# 140716_AriloTX_REV3_0_0_433MHZ_td.net
KiCad netlist of a schematic drawn in EAGLE
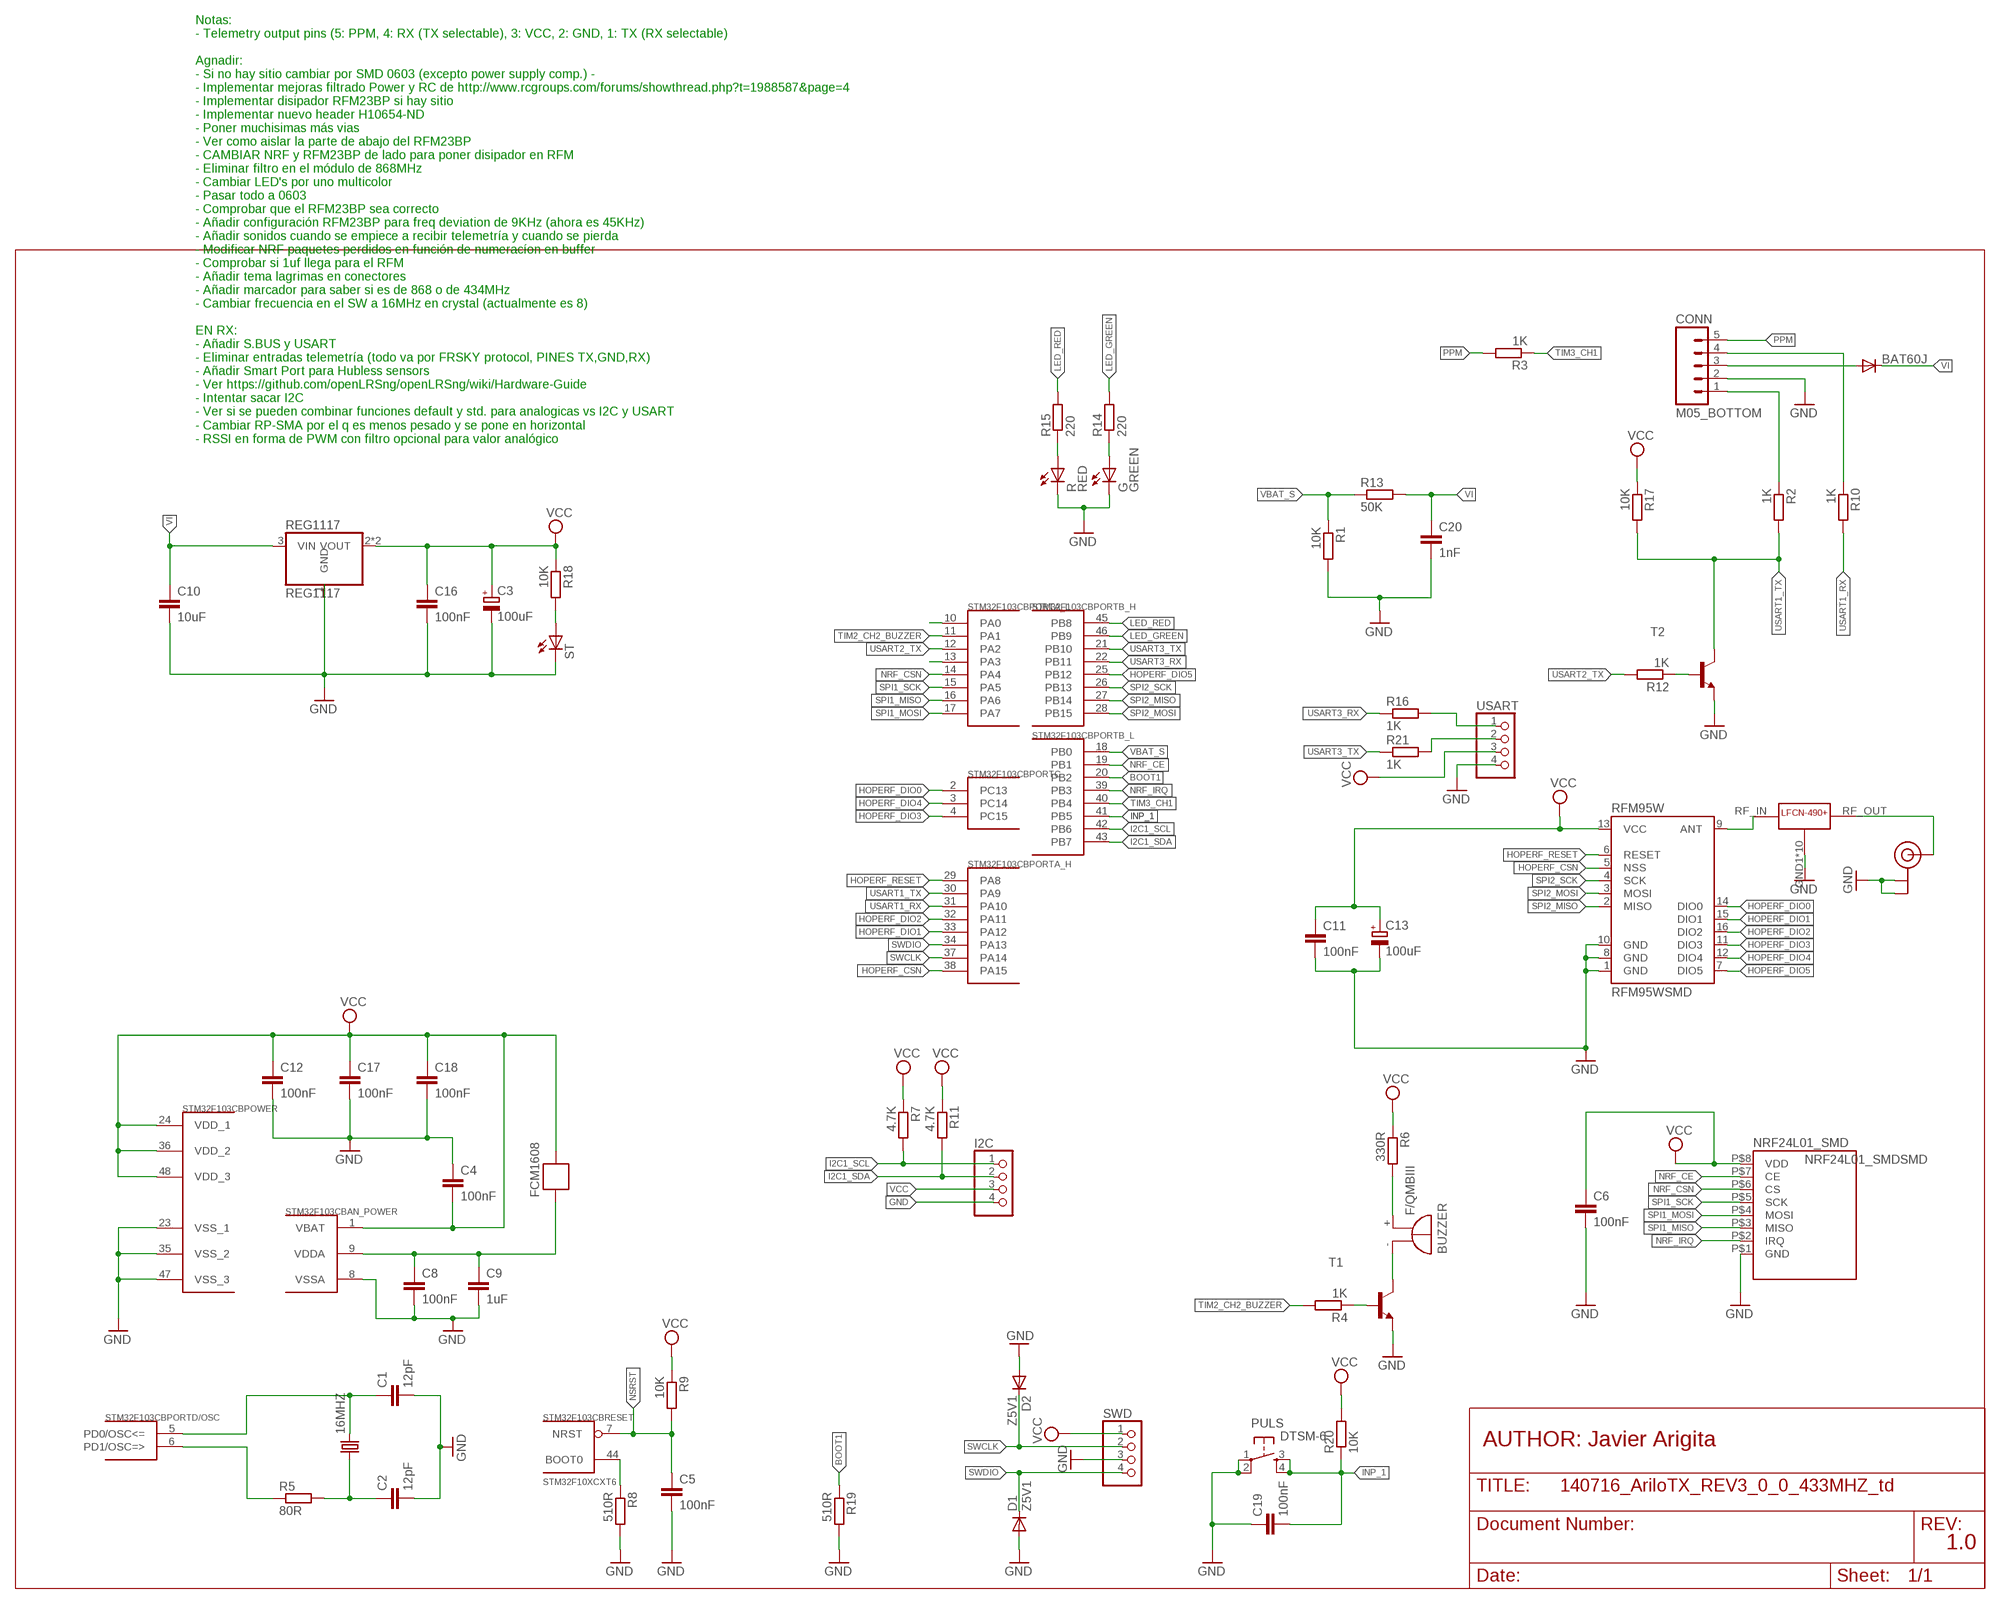
[diagram p0: schematic, sheet 1]

(export (version "E")
  (design (tool "Eeschema 10.0.6"))
  (components
    (comp (ref "16MHZ")
      (value "CRYSTAL5X3")
      (footprint "eagle-import:CRYSTAL-SMD-5X3")
      (libsource (lib "eagle-import") (part "CRYSTAL5X3"))
    )
    (comp (ref "BAT60J")
      (value "DIODE-SOD323-R")
      (footprint "eagle-import:SOD323-R")
      (libsource (lib "eagle-import") (part "DIODE-SOD323-R"))
    )
    (comp (ref "BUZZER")
      (value "F/QMBIII")
      (footprint "eagle-import:F_QMBIII")
      (libsource (lib "eagle-import") (part "F/QMBIII"))
    )
    (comp (ref "C1")
      (value "12pF")
      (footprint "eagle-import:C0603")
      (libsource (lib "eagle-import") (part "C-EUC0603"))
    )
    (comp (ref "C2")
      (value "12pF")
      (footprint "eagle-import:C0603")
      (libsource (lib "eagle-import") (part "C-EUC0603"))
    )
    (comp (ref "C3")
      (value "100uF")
      (footprint "eagle-import:SMC_B")
      (libsource (lib "eagle-import") (part "CPOL-EUSMCB"))
    )
    (comp (ref "C4")
      (value "100nF")
      (footprint "eagle-import:C0603")
      (libsource (lib "eagle-import") (part "C-EUC0603"))
    )
    (comp (ref "C5")
      (value "100nF")
      (footprint "eagle-import:C0603")
      (libsource (lib "eagle-import") (part "C-EUC0603"))
    )
    (comp (ref "C6")
      (value "100nF")
      (footprint "eagle-import:C0603")
      (libsource (lib "eagle-import") (part "C-EUC0603"))
    )
    (comp (ref "C8")
      (value "100nF")
      (footprint "eagle-import:C0603")
      (libsource (lib "eagle-import") (part "C-EUC0603"))
    )
    (comp (ref "C9")
      (value "1uF")
      (footprint "eagle-import:C0603")
      (libsource (lib "eagle-import") (part "C-EUC0603"))
    )
    (comp (ref "C10")
      (value "10uF")
      (footprint "eagle-import:C3216")
      (libsource (lib "eagle-import") (part "resistor_C-EUC3216"))
    )
    (comp (ref "C11")
      (value "100nF")
      (footprint "eagle-import:C0603")
      (libsource (lib "eagle-import") (part "C-EUC0603"))
    )
    (comp (ref "C12")
      (value "100nF")
      (footprint "eagle-import:C0603")
      (libsource (lib "eagle-import") (part "C-EUC0603"))
    )
    (comp (ref "C13")
      (value "100uF")
      (footprint "eagle-import:SMC_B")
      (libsource (lib "eagle-import") (part "CPOL-EUSMCB"))
    )
    (comp (ref "C16")
      (value "100nF")
      (footprint "eagle-import:C0603")
      (libsource (lib "eagle-import") (part "C-EUC0603"))
    )
    (comp (ref "C17")
      (value "100nF")
      (footprint "eagle-import:C0603")
      (libsource (lib "eagle-import") (part "C-EUC0603"))
    )
    (comp (ref "C18")
      (value "100nF")
      (footprint "eagle-import:C0603")
      (libsource (lib "eagle-import") (part "C-EUC0603"))
    )
    (comp (ref "C19")
      (value "100nF")
      (footprint "eagle-import:C0603")
      (libsource (lib "eagle-import") (part "C-EUC0603"))
    )
    (comp (ref "C20")
      (value "1nF")
      (footprint "eagle-import:C0603")
      (libsource (lib "eagle-import") (part "C-EUC0603"))
    )
    (comp (ref "CONN")
      (value "M05_BOTTOM")
      (footprint "eagle-import:M05_BOTTOM")
      (libsource (lib "eagle-import") (part "M05_BOTTOM"))
    )
    (comp (ref "D1")
      (value "Z5V1")
      (footprint "eagle-import:SOD323-R")
      (libsource (lib "eagle-import") (part "DIODE-SOD323-R"))
    )
    (comp (ref "D2")
      (value "Z5V1")
      (footprint "eagle-import:SOD323-R")
      (libsource (lib "eagle-import") (part "DIODE-SOD323-R"))
    )
    (comp (ref "FCM1608")
      (value "FERRITE-BEAD")
      (footprint "eagle-import:R0603")
      (libsource (lib "eagle-import") (part "FERRITE-BEAD"))
    )
    (comp (ref "G")
      (value "GREEN")
      (footprint "eagle-import:CHIP-LED0603")
      (libsource (lib "eagle-import") (part "LEDCHIP-LED0603"))
    )
    (comp (ref "I2C")
      (value "PINHD-1X4")
      (footprint "eagle-import:1X04")
      (libsource (lib "eagle-import") (part "PINHD-1X4"))
    )
    (comp (ref "LFCN490+")
      (value "LFCN490+")
      (footprint "eagle-import:LFCN490+")
      (libsource (lib "eagle-import") (part "LFCN490+"))
    )
    (comp (ref "NRF24L01_SMD")
      (value "NRF24L01_SMDSMD")
      (footprint "eagle-import:NRF24L01_SMD")
      (libsource (lib "eagle-import") (part "NRF24L01_SMDSMD"))
    )
    (comp (ref "PULS")
      (value "DTSM-6")
      (footprint "eagle-import:DTSM-6")
      (libsource (lib "eagle-import") (part "DTSM-6"))
    )
    (comp (ref "R")
      (value "RED")
      (footprint "eagle-import:CHIP-LED0603")
      (libsource (lib "eagle-import") (part "LEDCHIP-LED0603"))
    )
    (comp (ref "R1")
      (value "10K")
      (footprint "eagle-import:R0603")
      (libsource (lib "eagle-import") (part "R-EU_R0603"))
    )
    (comp (ref "R2")
      (value "1K")
      (footprint "eagle-import:R0603")
      (libsource (lib "eagle-import") (part "R-EU_R0603"))
    )
    (comp (ref "R3")
      (value "1K")
      (footprint "eagle-import:R0603")
      (libsource (lib "eagle-import") (part "R-EU_R0603"))
    )
    (comp (ref "R4")
      (value "1K")
      (footprint "eagle-import:R0603")
      (libsource (lib "eagle-import") (part "R-EU_R0603"))
    )
    (comp (ref "R5")
      (value "80R")
      (footprint "eagle-import:R0603")
      (libsource (lib "eagle-import") (part "R-EU_R0603"))
    )
    (comp (ref "R6")
      (value "330R")
      (footprint "eagle-import:R0603")
      (libsource (lib "eagle-import") (part "R-EU_R0603"))
    )
    (comp (ref "R7")
      (value "4.7K")
      (footprint "eagle-import:R0603")
      (libsource (lib "eagle-import") (part "R-EU_R0603"))
    )
    (comp (ref "R8")
      (value "510R")
      (footprint "eagle-import:R0603")
      (libsource (lib "eagle-import") (part "R-EU_R0603"))
    )
    (comp (ref "R9")
      (value "10K")
      (footprint "eagle-import:R0603")
      (libsource (lib "eagle-import") (part "R-EU_R0603"))
    )
    (comp (ref "R10")
      (value "1K")
      (footprint "eagle-import:R0603")
      (libsource (lib "eagle-import") (part "R-EU_R0603"))
    )
    (comp (ref "R11")
      (value "4.7K")
      (footprint "eagle-import:R0603")
      (libsource (lib "eagle-import") (part "R-EU_R0603"))
    )
    (comp (ref "R12")
      (value "1K")
      (footprint "eagle-import:R0603")
      (libsource (lib "eagle-import") (part "R-EU_R0603"))
    )
    (comp (ref "R13")
      (value "50K")
      (footprint "eagle-import:R0603")
      (libsource (lib "eagle-import") (part "R-EU_R0603"))
    )
    (comp (ref "R14")
      (value "220")
      (footprint "eagle-import:R0603")
      (libsource (lib "eagle-import") (part "R-EU_R0603"))
    )
    (comp (ref "R15")
      (value "220")
      (footprint "eagle-import:R0603")
      (libsource (lib "eagle-import") (part "R-EU_R0603"))
    )
    (comp (ref "R16")
      (value "1K")
      (footprint "eagle-import:R0603")
      (libsource (lib "eagle-import") (part "R-EU_R0603"))
    )
    (comp (ref "R17")
      (value "10K")
      (footprint "eagle-import:R0603")
      (libsource (lib "eagle-import") (part "R-EU_R0603"))
    )
    (comp (ref "R18")
      (value "10K")
      (footprint "eagle-import:R0603")
      (libsource (lib "eagle-import") (part "R-EU_R0603"))
    )
    (comp (ref "R19")
      (value "510R")
      (footprint "eagle-import:R0603")
      (libsource (lib "eagle-import") (part "R-EU_R0603"))
    )
    (comp (ref "R20")
      (value "10K")
      (footprint "eagle-import:R0603")
      (libsource (lib "eagle-import") (part "R-EU_R0603"))
    )
    (comp (ref "R21")
      (value "1K")
      (footprint "eagle-import:R0603")
      (libsource (lib "eagle-import") (part "R-EU_R0603"))
    )
    (comp (ref "REG1117")
      (value "REG1117")
      (footprint "eagle-import:SOT223")
      (libsource (lib "eagle-import") (part "REG1117"))
    )
    (comp (ref "RFM95W")
      (value "RFM95WSMD")
      (footprint "eagle-import:MISIEK_RFM95W_SMD")
      (libsource (lib "eagle-import") (part "MISIEK_RFM95WSMD"))
    )
    (comp (ref "ST")
      (value "LEDCHIP-LED0603")
      (footprint "eagle-import:CHIP-LED0603")
      (libsource (lib "eagle-import") (part "LEDCHIP-LED0603"))
    )
    (comp (ref "STM32F103CB")
      (value "STM32F10XCXT6")
      (footprint "eagle-import:TQFP48")
      (libsource (lib "eagle-import") (part "STM32F10XCXT6"))
    )
    (comp (ref "SWD")
      (value "PINHD-1X4")
      (footprint "eagle-import:1X04")
      (libsource (lib "eagle-import") (part "PINHD-1X4"))
    )
    (comp (ref "T1")
      (value "BC848-NPN-SOT23-BEC")
      (footprint "eagle-import:SOT23-BEC")
      (libsource (lib "eagle-import") (part "-NPN-SOT23-BECBC848"))
    )
    (comp (ref "T2")
      (value "BC848-NPN-SOT23-BEC")
      (footprint "eagle-import:SOT23-BEC")
      (libsource (lib "eagle-import") (part "-NPN-SOT23-BECBC848"))
    )
    (comp (ref "U.FL")
      (value "U.FL")
      (footprint "eagle-import:U.FL")
      (libsource (lib "eagle-import") (part "U.FL"))
    )
    (comp (ref "USART")
      (value "PINHD-1X4")
      (footprint "eagle-import:1X04")
      (libsource (lib "eagle-import") (part "PINHD-1X4"))
    )
  )
  (nets
    (net (code "1") (name "BOOT1") (class "Default")
      (node (ref "R19") (pin "1") (pinfunction "1_1") (pintype "passive"))
      (node (ref "STM32F103CB") (pin "20") (pinfunction "PB2_20") (pintype "bidirectional"))
    )
    (net (code "2") (name "GND") (class "Default")
      (node (ref "C1") (pin "2") (pinfunction "2_2") (pintype "passive"))
      (node (ref "C10") (pin "2") (pinfunction "2_2") (pintype "passive"))
      (node (ref "C11") (pin "2") (pinfunction "2_2") (pintype "passive"))
      (node (ref "C12") (pin "2") (pinfunction "2_2") (pintype "passive"))
      (node (ref "C13") (pin "-") (pinfunction "-_-") (pintype "passive"))
      (node (ref "C16") (pin "2") (pinfunction "2_2") (pintype "passive"))
      (node (ref "C17") (pin "2") (pinfunction "2_2") (pintype "passive"))
      (node (ref "C18") (pin "2") (pinfunction "2_2") (pintype "passive"))
      (node (ref "C19") (pin "1") (pinfunction "1_1") (pintype "passive"))
      (node (ref "C2") (pin "2") (pinfunction "2_2") (pintype "passive"))
      (node (ref "C20") (pin "2") (pinfunction "2_2") (pintype "passive"))
      (node (ref "C3") (pin "-") (pinfunction "-_-") (pintype "passive"))
      (node (ref "C4") (pin "1") (pinfunction "1_1") (pintype "passive"))
      (node (ref "C5") (pin "2") (pinfunction "2_2") (pintype "passive"))
      (node (ref "C6") (pin "2") (pinfunction "2_2") (pintype "passive"))
      (node (ref "C8") (pin "2") (pinfunction "2_2") (pintype "passive"))
      (node (ref "C9") (pin "2") (pinfunction "2_2") (pintype "passive"))
      (node (ref "CONN") (pin "2") (pinfunction "2_2") (pintype "passive"))
      (node (ref "D1") (pin "A") (pinfunction "A_A") (pintype "passive"))
      (node (ref "D2") (pin "A") (pinfunction "A_A") (pintype "passive"))
      (node (ref "G") (pin "C") (pinfunction "C_C") (pintype "passive"))
      (node (ref "I2C") (pin "4") (pinfunction "4_4") (pintype "passive"))
      (node (ref "LFCN490+") (pin "GND1") (pinfunction "GND_GND1") (pintype "bidirectional"))
      (node (ref "LFCN490+") (pin "GND10") (pinfunction "GND_GND10") (pintype "bidirectional"))
      (node (ref "LFCN490+") (pin "GND2") (pinfunction "GND_GND2") (pintype "bidirectional"))
      (node (ref "LFCN490+") (pin "GND3") (pinfunction "GND_GND3") (pintype "bidirectional"))
      (node (ref "LFCN490+") (pin "GND4") (pinfunction "GND_GND4") (pintype "bidirectional"))
      (node (ref "LFCN490+") (pin "GND5") (pinfunction "GND_GND5") (pintype "bidirectional"))
      (node (ref "LFCN490+") (pin "GND6") (pinfunction "GND_GND6") (pintype "bidirectional"))
      (node (ref "LFCN490+") (pin "GND7") (pinfunction "GND_GND7") (pintype "bidirectional"))
      (node (ref "LFCN490+") (pin "GND8") (pinfunction "GND_GND8") (pintype "bidirectional"))
      (node (ref "LFCN490+") (pin "GND9") (pinfunction "GND_GND9") (pintype "bidirectional"))
      (node (ref "NRF24L01_SMD") (pin "P$1") (pinfunction "GND_P$1") (pintype "power_in"))
      (node (ref "PULS") (pin "1") (pinfunction "1_1") (pintype "passive"))
      (node (ref "PULS") (pin "2") (pinfunction "2_2") (pintype "passive"))
      (node (ref "R") (pin "C") (pinfunction "C_C") (pintype "passive"))
      (node (ref "R1") (pin "2") (pinfunction "2_2") (pintype "passive"))
      (node (ref "R19") (pin "2") (pinfunction "2_2") (pintype "passive"))
      (node (ref "R8") (pin "2") (pinfunction "2_2") (pintype "passive"))
      (node (ref "REG1117") (pin "1") (pinfunction "GND_1") (pintype "power_in"))
      (node (ref "RFM95W") (pin "1") (pinfunction "GND_1") (pintype "power_in"))
      (node (ref "RFM95W") (pin "10") (pinfunction "GND_10") (pintype "power_in"))
      (node (ref "RFM95W") (pin "8") (pinfunction "GND_8") (pintype "power_in"))
      (node (ref "ST") (pin "C") (pinfunction "C_C") (pintype "passive"))
      (node (ref "STM32F103CB") (pin "23") (pinfunction "VSS_1_23") (pintype "power_in"))
      (node (ref "STM32F103CB") (pin "35") (pinfunction "VSS_2_35") (pintype "power_in"))
      (node (ref "STM32F103CB") (pin "47") (pinfunction "VSS_3_47") (pintype "power_in"))
      (node (ref "STM32F103CB") (pin "8") (pinfunction "VSSA_8") (pintype "power_in"))
      (node (ref "SWD") (pin "3") (pinfunction "3_3") (pintype "passive"))
      (node (ref "T1") (pin "E") (pinfunction "E_E") (pintype "passive"))
      (node (ref "T2") (pin "E") (pinfunction "E_E") (pintype "passive"))
      (node (ref "U.FL") (pin "P$1") (pinfunction "GND_P$1") (pintype "bidirectional"))
      (node (ref "U.FL") (pin "P$2") (pinfunction "GND_P$2") (pintype "bidirectional"))
      (node (ref "USART") (pin "4") (pinfunction "4_4") (pintype "passive"))
    )
    (net (code "3") (name "HOPERF_CSN") (class "Default")
      (node (ref "RFM95W") (pin "5") (pinfunction "NSS_5") (pintype "input"))
      (node (ref "STM32F103CB") (pin "38") (pinfunction "PA15_38") (pintype "bidirectional"))
    )
    (net (code "4") (name "HOPERF_DIO0") (class "Default")
      (node (ref "RFM95W") (pin "14") (pinfunction "DIO0_14") (pintype "input"))
      (node (ref "STM32F103CB") (pin "2") (pinfunction "PC13_2") (pintype "bidirectional"))
    )
    (net (code "5") (name "HOPERF_DIO1") (class "Default")
      (node (ref "RFM95W") (pin "15") (pinfunction "DIO1_15") (pintype "input"))
      (node (ref "STM32F103CB") (pin "33") (pinfunction "PA12_33") (pintype "bidirectional"))
    )
    (net (code "6") (name "HOPERF_DIO2") (class "Default")
      (node (ref "RFM95W") (pin "16") (pinfunction "DIO2_16") (pintype "input"))
      (node (ref "STM32F103CB") (pin "32") (pinfunction "PA11_32") (pintype "bidirectional"))
    )
    (net (code "7") (name "HOPERF_DIO3") (class "Default")
      (node (ref "RFM95W") (pin "11") (pinfunction "DIO3_11") (pintype "bidirectional"))
      (node (ref "STM32F103CB") (pin "4") (pinfunction "PC15_4") (pintype "bidirectional"))
    )
    (net (code "8") (name "HOPERF_DIO4") (class "Default")
      (node (ref "RFM95W") (pin "12") (pinfunction "DIO4_12") (pintype "bidirectional"))
      (node (ref "STM32F103CB") (pin "3") (pinfunction "PC14_3") (pintype "bidirectional"))
    )
    (net (code "9") (name "HOPERF_DIO5") (class "Default")
      (node (ref "RFM95W") (pin "7") (pinfunction "DIO5_7") (pintype "bidirectional"))
      (node (ref "STM32F103CB") (pin "25") (pinfunction "PB12_25") (pintype "bidirectional"))
    )
    (net (code "10") (name "HOPERF_RESET") (class "Default")
      (node (ref "RFM95W") (pin "6") (pinfunction "RESET_6") (pintype "output"))
      (node (ref "STM32F103CB") (pin "29") (pinfunction "PA8_29") (pintype "bidirectional"))
    )
    (net (code "11") (name "I2C1_SCL") (class "Default")
      (node (ref "I2C") (pin "1") (pinfunction "1_1") (pintype "passive"))
      (node (ref "R7") (pin "2") (pinfunction "2_2") (pintype "passive"))
      (node (ref "STM32F103CB") (pin "42") (pinfunction "PB6_42") (pintype "bidirectional"))
    )
    (net (code "12") (name "I2C1_SDA") (class "Default")
      (node (ref "I2C") (pin "2") (pinfunction "2_2") (pintype "passive"))
      (node (ref "R11") (pin "2") (pinfunction "2_2") (pintype "passive"))
      (node (ref "STM32F103CB") (pin "43") (pinfunction "PB7_43") (pintype "bidirectional"))
    )
    (net (code "13") (name "INP_1") (class "Default")
      (node (ref "C19") (pin "2") (pinfunction "2_2") (pintype "passive"))
      (node (ref "PULS") (pin "3") (pinfunction "3_3") (pintype "passive"))
      (node (ref "PULS") (pin "4") (pinfunction "4_4") (pintype "passive"))
      (node (ref "R20") (pin "1") (pinfunction "1_1") (pintype "passive"))
      (node (ref "STM32F103CB") (pin "41") (pinfunction "PB5_41") (pintype "bidirectional"))
    )
    (net (code "14") (name "LED_GREEN") (class "Default")
      (node (ref "R14") (pin "2") (pinfunction "2_2") (pintype "passive"))
      (node (ref "STM32F103CB") (pin "46") (pinfunction "PB9_46") (pintype "bidirectional"))
    )
    (net (code "15") (name "LED_RED") (class "Default")
      (node (ref "R15") (pin "2") (pinfunction "2_2") (pintype "passive"))
      (node (ref "STM32F103CB") (pin "45") (pinfunction "PB8_45") (pintype "bidirectional"))
    )
    (net (code "16") (name "NRF_CE") (class "Default")
      (node (ref "NRF24L01_SMD") (pin "P$7") (pinfunction "CE_P$7") (pintype "input"))
      (node (ref "STM32F103CB") (pin "19") (pinfunction "PB1_19") (pintype "bidirectional"))
    )
    (net (code "17") (name "NRF_CSN") (class "Default")
      (node (ref "NRF24L01_SMD") (pin "P$6") (pinfunction "CS_P$6") (pintype "input"))
      (node (ref "STM32F103CB") (pin "14") (pinfunction "PA4_14") (pintype "bidirectional"))
    )
    (net (code "18") (name "NRF_IRQ") (class "Default")
      (node (ref "NRF24L01_SMD") (pin "P$2") (pinfunction "IRQ_P$2") (pintype "output"))
      (node (ref "STM32F103CB") (pin "39") (pinfunction "PB3_39") (pintype "bidirectional"))
    )
    (net (code "19") (name "NSRST") (class "Default")
      (node (ref "C5") (pin "1") (pinfunction "1_1") (pintype "passive"))
      (node (ref "R9") (pin "2") (pinfunction "2_2") (pintype "passive"))
      (node (ref "STM32F103CB") (pin "7") (pinfunction "NRST_7") (pintype "input"))
    )
    (net (code "20") (name "Net-(16MHZ-2)") (class "Default")
      (node (ref "16MHZ") (pin "3") (pinfunction "2_3") (pintype "passive"))
      (node (ref "C1") (pin "1") (pinfunction "1_1") (pintype "passive"))
      (node (ref "STM32F103CB") (pin "5") (pinfunction "PD0/OSC<=_5") (pintype "bidirectional"))
    )
    (net (code "21") (name "Net-(16MHZ-Pad1)") (class "Default")
      (node (ref "16MHZ") (pin "1") (pinfunction "1_1") (pintype "passive"))
      (node (ref "C2") (pin "1") (pinfunction "1_1") (pintype "passive"))
      (node (ref "R5") (pin "2") (pinfunction "2_2") (pintype "passive"))
    )
    (net (code "22") (name "Net-(BAT60J-PadA)") (class "Default")
      (node (ref "BAT60J") (pin "A") (pinfunction "A_A") (pintype "passive"))
      (node (ref "CONN") (pin "3") (pinfunction "3_3") (pintype "passive"))
    )
    (net (code "23") (name "Net-(BUZZER-+)") (class "Default")
      (node (ref "BUZZER") (pin "-") (pinfunction "+_-") (pintype "passive"))
      (node (ref "T1") (pin "C") (pinfunction "C_C") (pintype "passive"))
    )
    (net (code "24") (name "Net-(BUZZER--)") (class "Default")
      (node (ref "BUZZER") (pin "+") (pinfunction "-_+") (pintype "passive"))
      (node (ref "R6") (pin "2") (pinfunction "2_2") (pintype "passive"))
    )
    (net (code "25") (name "Net-(CONN-Pad1)") (class "Default")
      (node (ref "CONN") (pin "1") (pinfunction "1_1") (pintype "passive"))
      (node (ref "R2") (pin "1") (pinfunction "1_1") (pintype "passive"))
    )
    (net (code "26") (name "Net-(CONN-Pad4)") (class "Default")
      (node (ref "CONN") (pin "4") (pinfunction "4_4") (pintype "passive"))
      (node (ref "R10") (pin "1") (pinfunction "1_1") (pintype "passive"))
    )
    (net (code "27") (name "Net-(FCM1608-P$2)") (class "Default")
      (node (ref "C8") (pin "1") (pinfunction "1_1") (pintype "passive"))
      (node (ref "C9") (pin "1") (pinfunction "1_1") (pintype "passive"))
      (node (ref "FCM1608") (pin "2") (pinfunction "P$2_2") (pintype "bidirectional"))
      (node (ref "STM32F103CB") (pin "9") (pinfunction "VDDA_9") (pintype "power_in"))
    )
    (net (code "28") (name "Net-(G-PadA)") (class "Default")
      (node (ref "G") (pin "A") (pinfunction "A_A") (pintype "passive"))
      (node (ref "R14") (pin "1") (pinfunction "1_1") (pintype "passive"))
    )
    (net (code "29") (name "Net-(LFCN490+-RF_INP)") (class "Default")
      (node (ref "LFCN490+") (pin "RF_IN") (pinfunction "RF_INP_RF_IN") (pintype "bidirectional"))
      (node (ref "RFM95W") (pin "9") (pinfunction "ANT_9") (pintype "bidirectional"))
    )
    (net (code "30") (name "Net-(LFCN490+-RF_OUTP)") (class "Default")
      (node (ref "LFCN490+") (pin "RF_OUT") (pinfunction "RF_OUTP_RF_OUT") (pintype "bidirectional"))
      (node (ref "U.FL") (pin "P$3") (pinfunction "SIGNAL_P$3") (pintype "bidirectional"))
    )
    (net (code "31") (name "Net-(R-PadA)") (class "Default")
      (node (ref "R") (pin "A") (pinfunction "A_A") (pintype "passive"))
      (node (ref "R15") (pin "1") (pinfunction "1_1") (pintype "passive"))
    )
    (net (code "32") (name "Net-(R4-Pad1)") (class "Default")
      (node (ref "R4") (pin "1") (pinfunction "1_1") (pintype "passive"))
      (node (ref "T1") (pin "B") (pinfunction "B_B") (pintype "passive"))
    )
    (net (code "33") (name "Net-(R12-Pad1)") (class "Default")
      (node (ref "R12") (pin "1") (pinfunction "1_1") (pintype "passive"))
      (node (ref "T2") (pin "B") (pinfunction "B_B") (pintype "passive"))
    )
    (net (code "34") (name "Net-(R16-Pad2)") (class "Default")
      (node (ref "R16") (pin "2") (pinfunction "2_2") (pintype "passive"))
      (node (ref "USART") (pin "1") (pinfunction "1_1") (pintype "passive"))
    )
    (net (code "35") (name "Net-(R18-Pad2)") (class "Default")
      (node (ref "R18") (pin "2") (pinfunction "2_2") (pintype "passive"))
      (node (ref "ST") (pin "A") (pinfunction "A_A") (pintype "passive"))
    )
    (net (code "36") (name "Net-(R21-Pad2)") (class "Default")
      (node (ref "R21") (pin "2") (pinfunction "2_2") (pintype "passive"))
      (node (ref "USART") (pin "2") (pinfunction "2_2") (pintype "passive"))
    )
    (net (code "37") (name "Net-(STM32F103CBG-PD1{slash}OSC=>)") (class "Default")
      (node (ref "R5") (pin "1") (pinfunction "1_1") (pintype "passive"))
      (node (ref "STM32F103CB") (pin "6") (pinfunction "PD1/OSC=>_6") (pintype "bidirectional"))
    )
    (net (code "38") (name "Net-(STM32F103CBI-BOOT0)") (class "Default")
      (node (ref "R8") (pin "1") (pinfunction "1_1") (pintype "passive"))
      (node (ref "STM32F103CB") (pin "44") (pinfunction "BOOT0_44") (pintype "input"))
    )
    (net (code "39") (name "PPM") (class "Default")
      (node (ref "CONN") (pin "5") (pinfunction "5_5") (pintype "passive"))
      (node (ref "R3") (pin "2") (pinfunction "2_2") (pintype "passive"))
    )
    (net (code "40") (name "SPI1_MISO") (class "Default")
      (node (ref "NRF24L01_SMD") (pin "P$3") (pinfunction "MISO_P$3") (pintype "output"))
      (node (ref "STM32F103CB") (pin "16") (pinfunction "PA6_16") (pintype "bidirectional"))
    )
    (net (code "41") (name "SPI1_MOSI") (class "Default")
      (node (ref "NRF24L01_SMD") (pin "P$4") (pinfunction "MOSI_P$4") (pintype "input"))
      (node (ref "STM32F103CB") (pin "17") (pinfunction "PA7_17") (pintype "bidirectional"))
    )
    (net (code "42") (name "SPI1_SCK") (class "Default")
      (node (ref "NRF24L01_SMD") (pin "P$5") (pinfunction "SCK_P$5") (pintype "input"))
      (node (ref "STM32F103CB") (pin "15") (pinfunction "PA5_15") (pintype "bidirectional"))
    )
    (net (code "43") (name "SPI2_MISO") (class "Default")
      (node (ref "RFM95W") (pin "2") (pinfunction "MISO_2") (pintype "output"))
      (node (ref "STM32F103CB") (pin "27") (pinfunction "PB14_27") (pintype "bidirectional"))
    )
    (net (code "44") (name "SPI2_MOSI") (class "Default")
      (node (ref "RFM95W") (pin "3") (pinfunction "MOSI_3") (pintype "input"))
      (node (ref "STM32F103CB") (pin "28") (pinfunction "PB15_28") (pintype "bidirectional"))
    )
    (net (code "45") (name "SPI2_SCK") (class "Default")
      (node (ref "RFM95W") (pin "4") (pinfunction "SCK_4") (pintype "input"))
      (node (ref "STM32F103CB") (pin "26") (pinfunction "PB13_26") (pintype "bidirectional"))
    )
    (net (code "46") (name "SWCLK") (class "Default")
      (node (ref "D2") (pin "C") (pinfunction "C_C") (pintype "passive"))
      (node (ref "STM32F103CB") (pin "37") (pinfunction "PA14_37") (pintype "bidirectional"))
      (node (ref "SWD") (pin "2") (pinfunction "2_2") (pintype "passive"))
    )
    (net (code "47") (name "SWDIO") (class "Default")
      (node (ref "D1") (pin "C") (pinfunction "C_C") (pintype "passive"))
      (node (ref "STM32F103CB") (pin "34") (pinfunction "PA13_34") (pintype "bidirectional"))
      (node (ref "SWD") (pin "4") (pinfunction "4_4") (pintype "passive"))
    )
    (net (code "48") (name "TIM2_CH2_BUZZER") (class "Default")
      (node (ref "R4") (pin "2") (pinfunction "2_2") (pintype "passive"))
      (node (ref "STM32F103CB") (pin "11") (pinfunction "PA1_11") (pintype "bidirectional"))
    )
    (net (code "49") (name "TIM3_CH1") (class "Default")
      (node (ref "R3") (pin "1") (pinfunction "1_1") (pintype "passive"))
      (node (ref "STM32F103CB") (pin "40") (pinfunction "PB4_40") (pintype "bidirectional"))
    )
    (net (code "50") (name "USART1_RX") (class "Default")
      (node (ref "R10") (pin "2") (pinfunction "2_2") (pintype "passive"))
      (node (ref "STM32F103CB") (pin "31") (pinfunction "PA10_31") (pintype "bidirectional"))
    )
    (net (code "51") (name "USART1_TX") (class "Default")
      (node (ref "R17") (pin "2") (pinfunction "2_2") (pintype "passive"))
      (node (ref "R2") (pin "2") (pinfunction "2_2") (pintype "passive"))
      (node (ref "STM32F103CB") (pin "30") (pinfunction "PA9_30") (pintype "bidirectional"))
      (node (ref "T2") (pin "C") (pinfunction "C_C") (pintype "passive"))
    )
    (net (code "52") (name "USART2_TX") (class "Default")
      (node (ref "R12") (pin "2") (pinfunction "2_2") (pintype "passive"))
      (node (ref "STM32F103CB") (pin "12") (pinfunction "PA2_12") (pintype "bidirectional"))
    )
    (net (code "53") (name "USART3_RX") (class "Default")
      (node (ref "R16") (pin "1") (pinfunction "1_1") (pintype "passive"))
      (node (ref "STM32F103CB") (pin "22") (pinfunction "PB11_22") (pintype "bidirectional"))
    )
    (net (code "54") (name "USART3_TX") (class "Default")
      (node (ref "R21") (pin "1") (pinfunction "1_1") (pintype "passive"))
      (node (ref "STM32F103CB") (pin "21") (pinfunction "PB10_21") (pintype "bidirectional"))
    )
    (net (code "55") (name "VBAT_S") (class "Default")
      (node (ref "R1") (pin "1") (pinfunction "1_1") (pintype "passive"))
      (node (ref "R13") (pin "1") (pinfunction "1_1") (pintype "passive"))
      (node (ref "STM32F103CB") (pin "18") (pinfunction "PB0_18") (pintype "bidirectional"))
    )
    (net (code "56") (name "VCC") (class "Default")
      (node (ref "C11") (pin "1") (pinfunction "1_1") (pintype "passive"))
      (node (ref "C12") (pin "1") (pinfunction "1_1") (pintype "passive"))
      (node (ref "C13") (pin "+") (pinfunction "+_+") (pintype "passive"))
      (node (ref "C16") (pin "1") (pinfunction "1_1") (pintype "passive"))
      (node (ref "C17") (pin "1") (pinfunction "1_1") (pintype "passive"))
      (node (ref "C18") (pin "1") (pinfunction "1_1") (pintype "passive"))
      (node (ref "C3") (pin "+") (pinfunction "+_+") (pintype "passive"))
      (node (ref "C4") (pin "2") (pinfunction "2_2") (pintype "passive"))
      (node (ref "C6") (pin "1") (pinfunction "1_1") (pintype "passive"))
      (node (ref "FCM1608") (pin "1") (pinfunction "P$1_1") (pintype "bidirectional"))
      (node (ref "I2C") (pin "3") (pinfunction "3_3") (pintype "passive"))
      (node (ref "NRF24L01_SMD") (pin "P$8") (pinfunction "VDD_P$8") (pintype "bidirectional"))
      (node (ref "R11") (pin "1") (pinfunction "1_1") (pintype "passive"))
      (node (ref "R17") (pin "1") (pinfunction "1_1") (pintype "passive"))
      (node (ref "R18") (pin "1") (pinfunction "1_1") (pintype "passive"))
      (node (ref "R20") (pin "2") (pinfunction "2_2") (pintype "passive"))
      (node (ref "R6") (pin "1") (pinfunction "1_1") (pintype "passive"))
      (node (ref "R7") (pin "1") (pinfunction "1_1") (pintype "passive"))
      (node (ref "R9") (pin "1") (pinfunction "1_1") (pintype "passive"))
      (node (ref "REG1117") (pin "2") (pinfunction "VOUT_2") (pintype "power_in"))
      (node (ref "REG1117") (pin "4") (pinfunction "VOUT_4") (pintype "power_in"))
      (node (ref "RFM95W") (pin "13") (pinfunction "VCC_13") (pintype "bidirectional"))
      (node (ref "STM32F103CB") (pin "1") (pinfunction "VBAT_1") (pintype "power_in"))
      (node (ref "STM32F103CB") (pin "24") (pinfunction "VDD_1_24") (pintype "power_in"))
      (node (ref "STM32F103CB") (pin "36") (pinfunction "VDD_2_36") (pintype "power_in"))
      (node (ref "STM32F103CB") (pin "48") (pinfunction "VDD_3_48") (pintype "power_in"))
      (node (ref "SWD") (pin "1") (pinfunction "1_1") (pintype "passive"))
      (node (ref "USART") (pin "3") (pinfunction "3_3") (pintype "passive"))
    )
    (net (code "57") (name "VI") (class "Default")
      (node (ref "BAT60J") (pin "C") (pinfunction "C_C") (pintype "passive"))
      (node (ref "C10") (pin "1") (pinfunction "1_1") (pintype "passive"))
      (node (ref "C20") (pin "1") (pinfunction "1_1") (pintype "passive"))
      (node (ref "R13") (pin "2") (pinfunction "2_2") (pintype "passive"))
      (node (ref "REG1117") (pin "3") (pinfunction "VIN_3") (pintype "input"))
    )
    (net (code "58") (name "unconnected-(STM32F103CBC-PA0-Pad10)") (class "Default")
      (node (ref "STM32F103CB") (pin "10") (pinfunction "PA0_10") (pintype "bidirectional"))
    )
    (net (code "59") (name "unconnected-(STM32F103CBC-PA3-Pad13)") (class "Default")
      (node (ref "STM32F103CB") (pin "13") (pinfunction "PA3_13") (pintype "bidirectional"))
    )
  )
)
